# SHDN-BSPD-S03-V00-VoltageDivider.net
KiCad netlist of a schematic drawn in Altium Designer
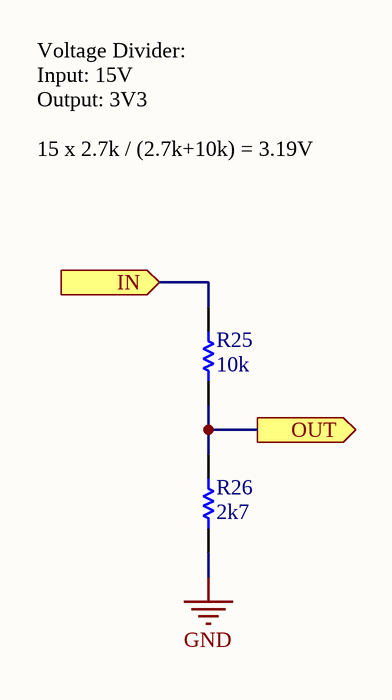
[diagram p0: SHDN-BSPD-S03-V00-VoltageDivider.SchDoc]

(export (version "E")
  (design (tool "Eeschema 10.0.6"))
  (components
    (comp (ref "R25")
      (value "10k")
      (footprint "Res_ThinFilm_0603")
      (description "Resistor, SMD, 10k, 0.1W, 5%, 0603")
      (libsource (lib "StandardResistors") (part "10k 5% 0603"))
    )
    (comp (ref "R26")
      (value "2k7")
      (footprint "Res_ThinFilm_0603")
      (description "Resistor, SMD, 2k7, 0.1W, 5%, 0603")
      (libsource (lib "StandardResistors") (part "2k7 5% 0603"))
    )
  )
  (nets
    (net (code "1") (name "/IN") (class "Default")
      (node (ref "R25") (pin "2") (pinfunction "2_2") (pintype "passive"))
    )
    (net (code "2") (name "/OUT") (class "Default")
      (node (ref "R25") (pin "1") (pinfunction "1_1") (pintype "passive"))
      (node (ref "R26") (pin "2") (pinfunction "2_2") (pintype "passive"))
    )
    (net (code "3") (name "GND") (class "Default")
      (node (ref "R26") (pin "1") (pinfunction "1_1") (pintype "passive"))
    )
  )
)
